# Test_ADC.net
KiCad netlist of a schematic drawn in EAGLE
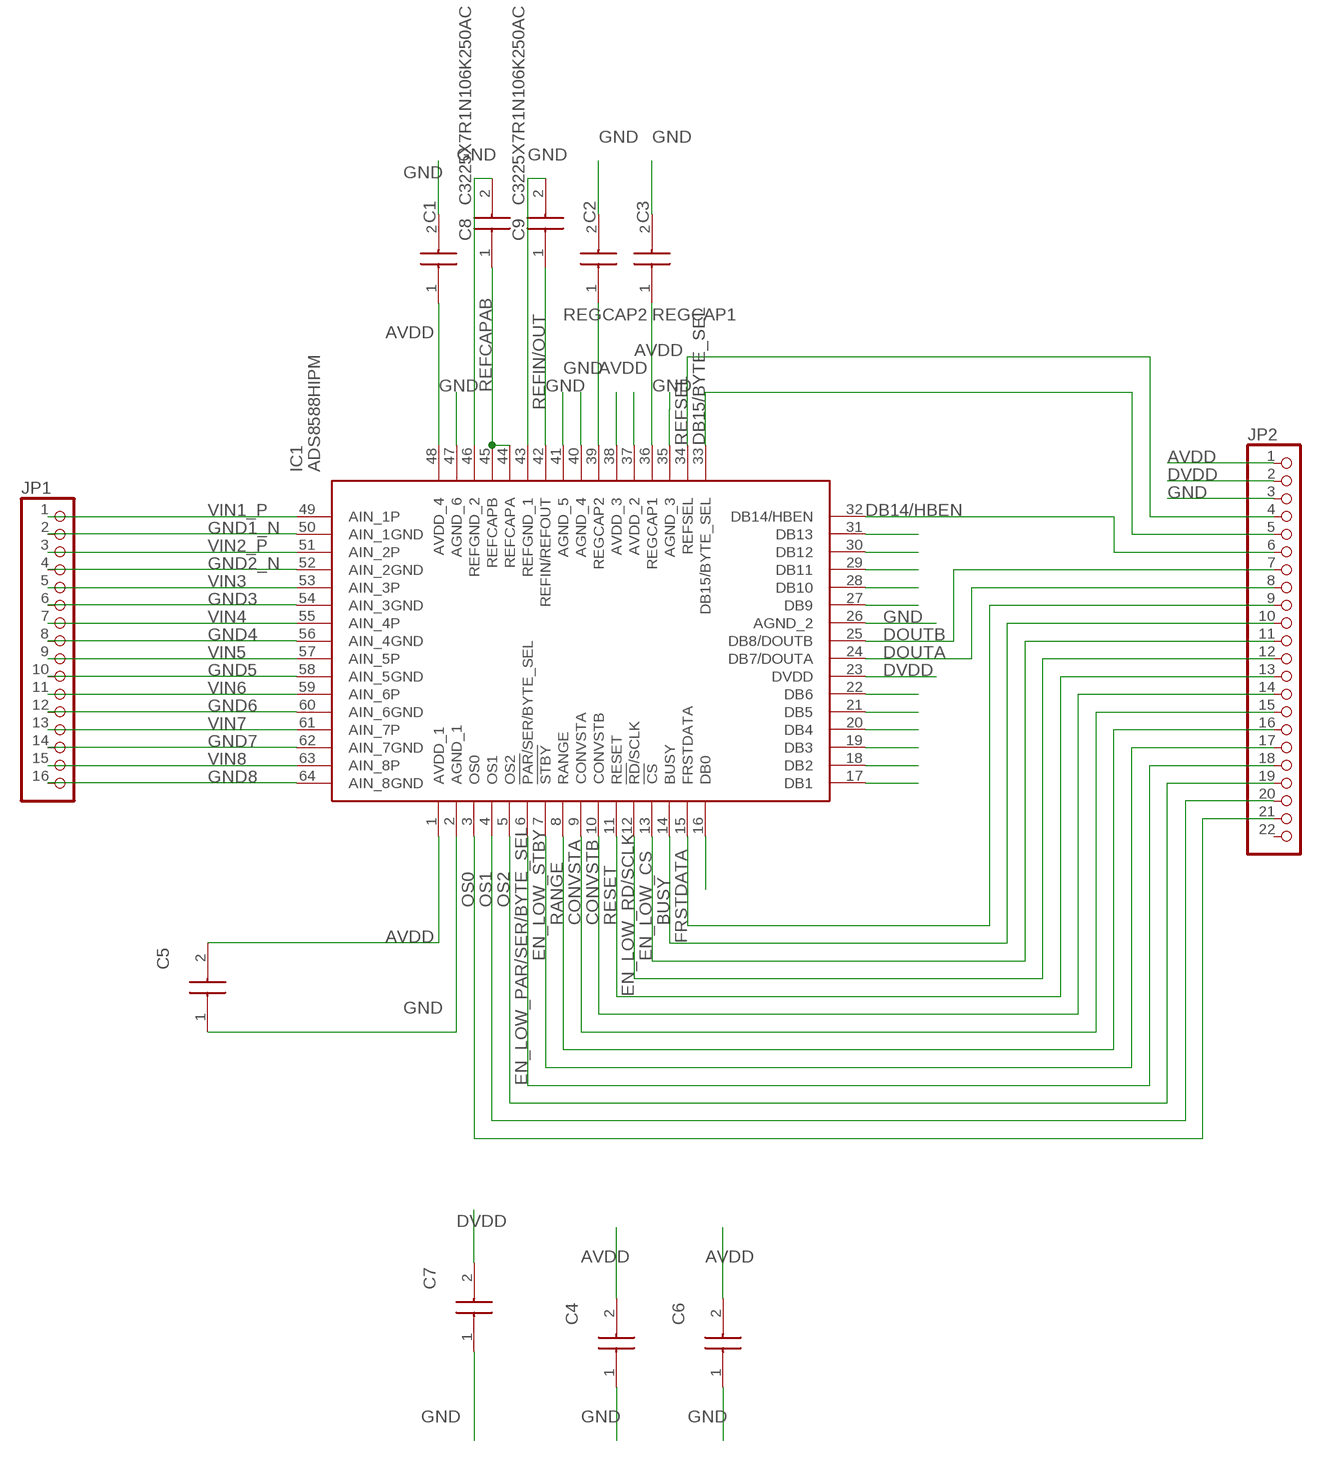
[diagram p0: schematic, sheet 1]

(export (version "E")
  (design (tool "Eeschema 10.0.6"))
  (components
    (comp (ref "C1")
      (value "06033C105KAT4A")
      (footprint "eagle-import:CAPC1608X90N")
      (fields (field (name "MOUSER_PART_NUMBER") "581-06033C105KAT4A"))
      (libsource (lib "eagle-import") (part "06033C105KAT4A"))
    )
    (comp (ref "C2")
      (value "06033C105KAT4A")
      (footprint "eagle-import:CAPC1608X90N")
      (fields (field (name "MOUSER_PART_NUMBER") "581-06033C105KAT4A"))
      (libsource (lib "eagle-import") (part "06033C105KAT4A"))
    )
    (comp (ref "C3")
      (value "06033C105KAT4A")
      (footprint "eagle-import:CAPC1608X90N")
      (fields (field (name "MOUSER_PART_NUMBER") "581-06033C105KAT4A"))
      (libsource (lib "eagle-import") (part "06033C105KAT4A"))
    )
    (comp (ref "C4")
      (value "06033C105KAT4A")
      (footprint "eagle-import:CAPC1608X90N")
      (fields (field (name "MOUSER_PART_NUMBER") "581-06033C105KAT4A"))
      (libsource (lib "eagle-import") (part "06033C105KAT4A"))
    )
    (comp (ref "C5")
      (value "06033C105KAT4A")
      (footprint "eagle-import:CAPC1608X90N")
      (fields (field (name "MOUSER_PART_NUMBER") "581-06033C105KAT4A"))
      (libsource (lib "eagle-import") (part "06033C105KAT4A"))
    )
    (comp (ref "C6")
      (value "06033C105KAT4A")
      (footprint "eagle-import:CAPC1608X90N")
      (fields (field (name "MOUSER_PART_NUMBER") "581-06033C105KAT4A"))
      (libsource (lib "eagle-import") (part "06033C105KAT4A"))
    )
    (comp (ref "C7")
      (value "06033C105KAT4A")
      (footprint "eagle-import:CAPC1608X90N")
      (fields (field (name "MOUSER_PART_NUMBER") "581-06033C105KAT4A"))
      (libsource (lib "eagle-import") (part "06033C105KAT4A"))
    )
    (comp (ref "C8")
      (value "C3225X7R1N106K250AC")
      (footprint "eagle-import:CAPC3225X230N")
      (fields (field (name "MOUSER_PART_NUMBER") "810-C3225X7R1N106K25"))
      (libsource (lib "eagle-import") (part "C3225X7R1N106K250AC"))
    )
    (comp (ref "C9")
      (value "C3225X7R1N106K250AC")
      (footprint "eagle-import:CAPC3225X230N")
      (fields (field (name "MOUSER_PART_NUMBER") "810-C3225X7R1N106K25"))
      (libsource (lib "eagle-import") (part "C3225X7R1N106K250AC"))
    )
    (comp (ref "IC1")
      (value "ADS8588HIPM")
      (footprint "eagle-import:QFP50P1200X1200X160-64N")
      (fields (field (name "MOUSER_PART_NUMBER") "595-ADS8588HIPM"))
      (libsource (lib "eagle-import") (part "ADS8588HIPM"))
    )
    (comp (ref "JP1")
      (value "PINHD-1X16")
      (footprint "eagle-import:1X16")
      (libsource (lib "eagle-import") (part "PINHD-1X16"))
    )
    (comp (ref "JP2")
      (value "PINHD-1X22")
      (footprint "eagle-import:1X22")
      (libsource (lib "eagle-import") (part "PINHD-1X22"))
    )
  )
  (nets
    (net (code "1") (name "/AVDD") (class "Default")
      (node (ref "C1") (pin "1") (pinfunction "1_1") (pintype "bidirectional"))
      (node (ref "C4") (pin "2") (pinfunction "2_2") (pintype "bidirectional"))
      (node (ref "C5") (pin "2") (pinfunction "2_2") (pintype "bidirectional"))
      (node (ref "C6") (pin "2") (pinfunction "2_2") (pintype "bidirectional"))
      (node (ref "IC1") (pin "1") (pinfunction "AVDD_1_1") (pintype "power_in"))
      (node (ref "IC1") (pin "37") (pinfunction "AVDD_2_37") (pintype "power_in"))
      (node (ref "IC1") (pin "38") (pinfunction "AVDD_3_38") (pintype "power_in"))
      (node (ref "IC1") (pin "48") (pinfunction "AVDD_4_48") (pintype "power_in"))
      (node (ref "JP2") (pin "1") (pinfunction "1_1") (pintype "passive"))
    )
    (net (code "2") (name "/BUSY") (class "Default")
      (node (ref "IC1") (pin "14") (pinfunction "BUSY_14") (pintype "output"))
      (node (ref "JP2") (pin "10") (pinfunction "10_10") (pintype "passive"))
    )
    (net (code "3") (name "/CONVSTA") (class "Default")
      (node (ref "IC1") (pin "9") (pinfunction "CONVSTA_9") (pintype "input"))
      (node (ref "JP2") (pin "15") (pinfunction "15_15") (pintype "passive"))
    )
    (net (code "4") (name "/CONVSTB") (class "Default")
      (node (ref "IC1") (pin "10") (pinfunction "CONVSTB_10") (pintype "input"))
      (node (ref "JP2") (pin "14") (pinfunction "14_14") (pintype "passive"))
    )
    (net (code "5") (name "/DB14{slash}HBEN") (class "Default")
      (node (ref "IC1") (pin "32") (pinfunction "DB14/HBEN_32") (pintype "bidirectional"))
      (node (ref "JP2") (pin "6") (pinfunction "6_6") (pintype "passive"))
    )
    (net (code "6") (name "/DB15{slash}BYTE_SEL") (class "Default")
      (node (ref "IC1") (pin "33") (pinfunction "DB15/BYTE_SEL_33") (pintype "bidirectional"))
      (node (ref "JP2") (pin "5") (pinfunction "5_5") (pintype "passive"))
    )
    (net (code "7") (name "/DOUTA") (class "Default")
      (node (ref "IC1") (pin "24") (pinfunction "DB7/DOUTA_24") (pintype "output"))
      (node (ref "JP2") (pin "8") (pinfunction "8_8") (pintype "passive"))
    )
    (net (code "8") (name "/DOUTB") (class "Default")
      (node (ref "IC1") (pin "25") (pinfunction "DB8/DOUTB_25") (pintype "output"))
      (node (ref "JP2") (pin "7") (pinfunction "7_7") (pintype "passive"))
    )
    (net (code "9") (name "/DVDD") (class "Default")
      (node (ref "C7") (pin "2") (pinfunction "2_2") (pintype "bidirectional"))
      (node (ref "IC1") (pin "23") (pinfunction "DVDD_23") (pintype "power_in"))
      (node (ref "JP2") (pin "2") (pinfunction "2_2") (pintype "passive"))
    )
    (net (code "10") (name "/EN_LOW_CS") (class "Default")
      (node (ref "IC1") (pin "13") (pinfunction "~{CS}_13") (pintype "input"))
      (node (ref "JP2") (pin "11") (pinfunction "11_11") (pintype "passive"))
    )
    (net (code "11") (name "/EN_LOW_PAR{slash}SER{slash}BYTE_SEL") (class "Default")
      (node (ref "IC1") (pin "6") (pinfunction "~{PAR}/SER/BYTE_SEL_6") (pintype "input"))
      (node (ref "JP2") (pin "18") (pinfunction "18_18") (pintype "passive"))
    )
    (net (code "12") (name "/EN_LOW_RD{slash}SCLK") (class "Default")
      (node (ref "IC1") (pin "12") (pinfunction "~{RD}/SCLK_12") (pintype "input"))
      (node (ref "JP2") (pin "12") (pinfunction "12_12") (pintype "passive"))
    )
    (net (code "13") (name "/EN_LOW_STBY") (class "Default")
      (node (ref "IC1") (pin "7") (pinfunction "~{STBY}_7") (pintype "input"))
      (node (ref "JP2") (pin "17") (pinfunction "17_17") (pintype "passive"))
    )
    (net (code "14") (name "/FRSTDATA") (class "Default")
      (node (ref "IC1") (pin "15") (pinfunction "FRSTDATA_15") (pintype "output"))
      (node (ref "JP2") (pin "9") (pinfunction "9_9") (pintype "passive"))
    )
    (net (code "15") (name "/GND") (class "Default")
      (node (ref "C1") (pin "2") (pinfunction "2_2") (pintype "bidirectional"))
      (node (ref "C2") (pin "2") (pinfunction "2_2") (pintype "bidirectional"))
      (node (ref "C3") (pin "2") (pinfunction "2_2") (pintype "bidirectional"))
      (node (ref "C4") (pin "1") (pinfunction "1_1") (pintype "bidirectional"))
      (node (ref "C5") (pin "1") (pinfunction "1_1") (pintype "bidirectional"))
      (node (ref "C6") (pin "1") (pinfunction "1_1") (pintype "bidirectional"))
      (node (ref "C7") (pin "1") (pinfunction "1_1") (pintype "bidirectional"))
      (node (ref "C8") (pin "2") (pinfunction "2_2") (pintype "bidirectional"))
      (node (ref "C9") (pin "2") (pinfunction "2_2") (pintype "bidirectional"))
      (node (ref "IC1") (pin "2") (pinfunction "AGND_1_2") (pintype "power_in"))
      (node (ref "IC1") (pin "26") (pinfunction "AGND_2_26") (pintype "power_in"))
      (node (ref "IC1") (pin "35") (pinfunction "AGND_3_35") (pintype "power_in"))
      (node (ref "IC1") (pin "40") (pinfunction "AGND_4_40") (pintype "power_in"))
      (node (ref "IC1") (pin "41") (pinfunction "AGND_5_41") (pintype "power_in"))
      (node (ref "IC1") (pin "43") (pinfunction "REFGND_1_43") (pintype "power_in"))
      (node (ref "IC1") (pin "46") (pinfunction "REFGND_2_46") (pintype "power_in"))
      (node (ref "IC1") (pin "47") (pinfunction "AGND_6_47") (pintype "power_in"))
      (node (ref "JP2") (pin "3") (pinfunction "3_3") (pintype "passive"))
    )
    (net (code "16") (name "/GND1_N") (class "Default")
      (node (ref "IC1") (pin "50") (pinfunction "AIN_1GND_50") (pintype "input"))
      (node (ref "JP1") (pin "2") (pinfunction "2_2") (pintype "passive"))
    )
    (net (code "17") (name "/GND2_N") (class "Default")
      (node (ref "IC1") (pin "52") (pinfunction "AIN_2GND_52") (pintype "input"))
      (node (ref "JP1") (pin "4") (pinfunction "4_4") (pintype "passive"))
    )
    (net (code "18") (name "/GND3") (class "Default")
      (node (ref "IC1") (pin "54") (pinfunction "AIN_3GND_54") (pintype "input"))
      (node (ref "JP1") (pin "6") (pinfunction "6_6") (pintype "passive"))
    )
    (net (code "19") (name "/GND4") (class "Default")
      (node (ref "IC1") (pin "56") (pinfunction "AIN_4GND_56") (pintype "input"))
      (node (ref "JP1") (pin "8") (pinfunction "8_8") (pintype "passive"))
    )
    (net (code "20") (name "/GND5") (class "Default")
      (node (ref "IC1") (pin "58") (pinfunction "AIN_5GND_58") (pintype "input"))
      (node (ref "JP1") (pin "10") (pinfunction "10_10") (pintype "passive"))
    )
    (net (code "21") (name "/GND6") (class "Default")
      (node (ref "IC1") (pin "60") (pinfunction "AIN_6GND_60") (pintype "input"))
      (node (ref "JP1") (pin "12") (pinfunction "12_12") (pintype "passive"))
    )
    (net (code "22") (name "/GND7") (class "Default")
      (node (ref "IC1") (pin "62") (pinfunction "AIN_7GND_62") (pintype "input"))
      (node (ref "JP1") (pin "14") (pinfunction "14_14") (pintype "passive"))
    )
    (net (code "23") (name "/GND8") (class "Default")
      (node (ref "IC1") (pin "64") (pinfunction "AIN_8GND_64") (pintype "input"))
      (node (ref "JP1") (pin "16") (pinfunction "16_16") (pintype "passive"))
    )
    (net (code "24") (name "/OS0") (class "Default")
      (node (ref "IC1") (pin "3") (pinfunction "OS0_3") (pintype "input"))
      (node (ref "JP2") (pin "21") (pinfunction "21_21") (pintype "passive"))
    )
    (net (code "25") (name "/OS1") (class "Default")
      (node (ref "IC1") (pin "4") (pinfunction "OS1_4") (pintype "input"))
      (node (ref "JP2") (pin "20") (pinfunction "20_20") (pintype "passive"))
    )
    (net (code "26") (name "/OS2") (class "Default")
      (node (ref "IC1") (pin "5") (pinfunction "OS2_5") (pintype "input"))
      (node (ref "JP2") (pin "19") (pinfunction "19_19") (pintype "passive"))
    )
    (net (code "27") (name "/RANGE") (class "Default")
      (node (ref "IC1") (pin "8") (pinfunction "RANGE_8") (pintype "input"))
      (node (ref "JP2") (pin "16") (pinfunction "16_16") (pintype "passive"))
    )
    (net (code "28") (name "/REFCAPAB") (class "Default")
      (node (ref "C8") (pin "1") (pinfunction "1_1") (pintype "bidirectional"))
      (node (ref "IC1") (pin "44") (pinfunction "REFCAPA_44") (pintype "output"))
      (node (ref "IC1") (pin "45") (pinfunction "REFCAPB_45") (pintype "output"))
    )
    (net (code "29") (name "/REFIN{slash}OUT") (class "Default")
      (node (ref "C9") (pin "1") (pinfunction "1_1") (pintype "bidirectional"))
      (node (ref "IC1") (pin "42") (pinfunction "REFIN/REFOUT_42") (pintype "bidirectional"))
    )
    (net (code "30") (name "/REFSEL") (class "Default")
      (node (ref "IC1") (pin "34") (pinfunction "REFSEL_34") (pintype "input"))
      (node (ref "JP2") (pin "4") (pinfunction "4_4") (pintype "passive"))
    )
    (net (code "31") (name "/REGCAP1") (class "Default")
      (node (ref "C3") (pin "1") (pinfunction "1_1") (pintype "bidirectional"))
      (node (ref "IC1") (pin "36") (pinfunction "REGCAP1_36") (pintype "output"))
    )
    (net (code "32") (name "/REGCAP2") (class "Default")
      (node (ref "C2") (pin "1") (pinfunction "1_1") (pintype "bidirectional"))
      (node (ref "IC1") (pin "39") (pinfunction "REGCAP2_39") (pintype "output"))
    )
    (net (code "33") (name "/RESET") (class "Default")
      (node (ref "IC1") (pin "11") (pinfunction "RESET_11") (pintype "input"))
      (node (ref "JP2") (pin "13") (pinfunction "13_13") (pintype "passive"))
    )
    (net (code "34") (name "/VIN1_P") (class "Default")
      (node (ref "IC1") (pin "49") (pinfunction "AIN_1P_49") (pintype "input"))
      (node (ref "JP1") (pin "1") (pinfunction "1_1") (pintype "passive"))
    )
    (net (code "35") (name "/VIN2_P") (class "Default")
      (node (ref "IC1") (pin "51") (pinfunction "AIN_2P_51") (pintype "input"))
      (node (ref "JP1") (pin "3") (pinfunction "3_3") (pintype "passive"))
    )
    (net (code "36") (name "/VIN3") (class "Default")
      (node (ref "IC1") (pin "53") (pinfunction "AIN_3P_53") (pintype "input"))
      (node (ref "JP1") (pin "5") (pinfunction "5_5") (pintype "passive"))
    )
    (net (code "37") (name "/VIN4") (class "Default")
      (node (ref "IC1") (pin "55") (pinfunction "AIN_4P_55") (pintype "input"))
      (node (ref "JP1") (pin "7") (pinfunction "7_7") (pintype "passive"))
    )
    (net (code "38") (name "/VIN5") (class "Default")
      (node (ref "IC1") (pin "57") (pinfunction "AIN_5P_57") (pintype "input"))
      (node (ref "JP1") (pin "9") (pinfunction "9_9") (pintype "passive"))
    )
    (net (code "39") (name "/VIN6") (class "Default")
      (node (ref "IC1") (pin "59") (pinfunction "AIN_6P_59") (pintype "input"))
      (node (ref "JP1") (pin "11") (pinfunction "11_11") (pintype "passive"))
    )
    (net (code "40") (name "/VIN7") (class "Default")
      (node (ref "IC1") (pin "61") (pinfunction "AIN_7P_61") (pintype "input"))
      (node (ref "JP1") (pin "13") (pinfunction "13_13") (pintype "passive"))
    )
    (net (code "41") (name "/VIN8") (class "Default")
      (node (ref "IC1") (pin "63") (pinfunction "AIN_8P_63") (pintype "input"))
      (node (ref "JP1") (pin "15") (pinfunction "15_15") (pintype "passive"))
    )
    (net (code "42") (name "unconnected-(IC1-DB0-Pad16)") (class "Default")
      (node (ref "IC1") (pin "16") (pinfunction "DB0_16") (pintype "output"))
    )
    (net (code "43") (name "unconnected-(IC1-DB1-Pad17)") (class "Default")
      (node (ref "IC1") (pin "17") (pinfunction "DB1_17") (pintype "output"))
    )
    (net (code "44") (name "unconnected-(IC1-DB2-Pad18)") (class "Default")
      (node (ref "IC1") (pin "18") (pinfunction "DB2_18") (pintype "output"))
    )
    (net (code "45") (name "unconnected-(IC1-DB3-Pad19)") (class "Default")
      (node (ref "IC1") (pin "19") (pinfunction "DB3_19") (pintype "output"))
    )
    (net (code "46") (name "unconnected-(IC1-DB4-Pad20)") (class "Default")
      (node (ref "IC1") (pin "20") (pinfunction "DB4_20") (pintype "output"))
    )
    (net (code "47") (name "unconnected-(IC1-DB5-Pad21)") (class "Default")
      (node (ref "IC1") (pin "21") (pinfunction "DB5_21") (pintype "output"))
    )
    (net (code "48") (name "unconnected-(IC1-DB6-Pad22)") (class "Default")
      (node (ref "IC1") (pin "22") (pinfunction "DB6_22") (pintype "output"))
    )
    (net (code "49") (name "unconnected-(IC1-DB9-Pad27)") (class "Default")
      (node (ref "IC1") (pin "27") (pinfunction "DB9_27") (pintype "output"))
    )
    (net (code "50") (name "unconnected-(IC1-DB10-Pad28)") (class "Default")
      (node (ref "IC1") (pin "28") (pinfunction "DB10_28") (pintype "output"))
    )
    (net (code "51") (name "unconnected-(IC1-DB11-Pad29)") (class "Default")
      (node (ref "IC1") (pin "29") (pinfunction "DB11_29") (pintype "output"))
    )
    (net (code "52") (name "unconnected-(IC1-DB12-Pad30)") (class "Default")
      (node (ref "IC1") (pin "30") (pinfunction "DB12_30") (pintype "output"))
    )
    (net (code "53") (name "unconnected-(IC1-DB13-Pad31)") (class "Default")
      (node (ref "IC1") (pin "31") (pinfunction "DB13_31") (pintype "output"))
    )
    (net (code "54") (name "unconnected-(JP2-Pad22)") (class "Default")
      (node (ref "JP2") (pin "22") (pinfunction "22_22") (pintype "passive"))
    )
  )
)
